# Debugger.net
KiCad netlist of a schematic drawn in Altium Designer
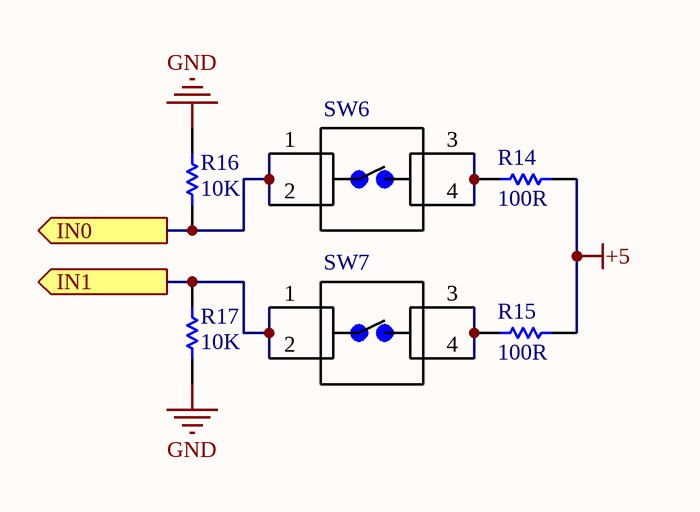
[diagram p0: Debugger.SchDoc]

(export (version "E")
  (design (tool "Eeschema 10.0.6"))
  (components
    (comp (ref "R14")
      (value "100R")
      (footprint "RESC0805(2012)_L")
      (description "100R 0.125W 1% 0805 (2012 Metric)  SMD")
      (fields (field (name "POWER") "0.125 W") (field (name "TOLERANCE") "1 %"))
      (libsource (lib "Altium Content Vault") (part "RES"))
    )
    (comp (ref "R15")
      (value "100R")
      (footprint "RESC0805(2012)_L")
      (description "100R 0.125W 1% 0805 (2012 Metric)  SMD")
      (fields (field (name "POWER") "0.125 W") (field (name "TOLERANCE") "1 %"))
      (libsource (lib "Altium Content Vault") (part "RES"))
    )
    (comp (ref "R16")
      (value "10K")
      (footprint "RESC0805(2012)_L")
      (description "10K2 0.125W 1% 0805 (2012 Metric)  SMD")
      (fields (field (name "TOLERANCE") "1 %") (field (name "POWER") "0.125 W"))
      (libsource (lib "Altium Content Vault") (part "RES"))
    )
    (comp (ref "R17")
      (value "10K")
      (footprint "RESC0805(2012)_L")
      (description "10K2 0.125W 1% 0805 (2012 Metric)  SMD")
      (fields (field (name "TOLERANCE") "1 %") (field (name "POWER") "0.125 W"))
      (libsource (lib "Altium Content Vault") (part "RES"))
    )
    (comp (ref "SW6")
      (value "1825910-7")
      (footprint "Switch 6mm 24V (NO)")
      (description "FSM4JAH=6MM TACT SWITCH, HIGH TEMP")
      (fields (field (name "MF") "TE Connectivity") (field (name "DIGI-KEY_PART_NUMBER") "450-1804-ND"))
      (libsource (lib "Husky Robotics Standard Library 2019-2020") (part "Switch 6mm 24V (NO)"))
    )
    (comp (ref "SW7")
      (value "1825910-7")
      (footprint "Switch 6mm 24V (NO)")
      (description "FSM4JAH=6MM TACT SWITCH, HIGH TEMP")
      (fields (field (name "MF") "TE Connectivity") (field (name "DIGI-KEY_PART_NUMBER") "450-1804-ND"))
      (libsource (lib "Husky Robotics Standard Library 2019-2020") (part "Switch 6mm 24V (NO)"))
    )
  )
  (nets
    (net (code "1") (name "+5") (class "Default")
      (node (ref "R14") (pin "1") (pinfunction "1_1") (pintype "passive"))
      (node (ref "R15") (pin "1") (pinfunction "1_1") (pintype "passive"))
    )
    (net (code "2") (name "/IN0") (class "Default")
      (node (ref "R16") (pin "1") (pinfunction "1_1") (pintype "passive"))
      (node (ref "SW6") (pin "1") (pinfunction "1_1") (pintype "passive"))
      (node (ref "SW6") (pin "2") (pinfunction "2_2") (pintype "passive"))
    )
    (net (code "3") (name "/IN1") (class "Default")
      (node (ref "R17") (pin "2") (pinfunction "2_2") (pintype "passive"))
      (node (ref "SW7") (pin "1") (pinfunction "1_1") (pintype "passive"))
      (node (ref "SW7") (pin "2") (pinfunction "2_2") (pintype "passive"))
    )
    (net (code "4") (name "GND") (class "Default")
      (node (ref "R16") (pin "2") (pinfunction "2_2") (pintype "passive"))
      (node (ref "R17") (pin "1") (pinfunction "1_1") (pintype "passive"))
    )
    (net (code "5") (name "Net-(R14-Pad2)") (class "Default")
      (node (ref "R14") (pin "2") (pinfunction "2_2") (pintype "passive"))
      (node (ref "SW6") (pin "3") (pinfunction "3_3") (pintype "passive"))
      (node (ref "SW6") (pin "4") (pinfunction "4_4") (pintype "passive"))
    )
    (net (code "6") (name "Net-(R15-Pad2)") (class "Default")
      (node (ref "R15") (pin "2") (pinfunction "2_2") (pintype "passive"))
      (node (ref "SW7") (pin "3") (pinfunction "3_3") (pintype "passive"))
      (node (ref "SW7") (pin "4") (pinfunction "4_4") (pintype "passive"))
    )
  )
)
